# I2CKeypad.net
KiCad netlist of a schematic drawn in Altium Designer
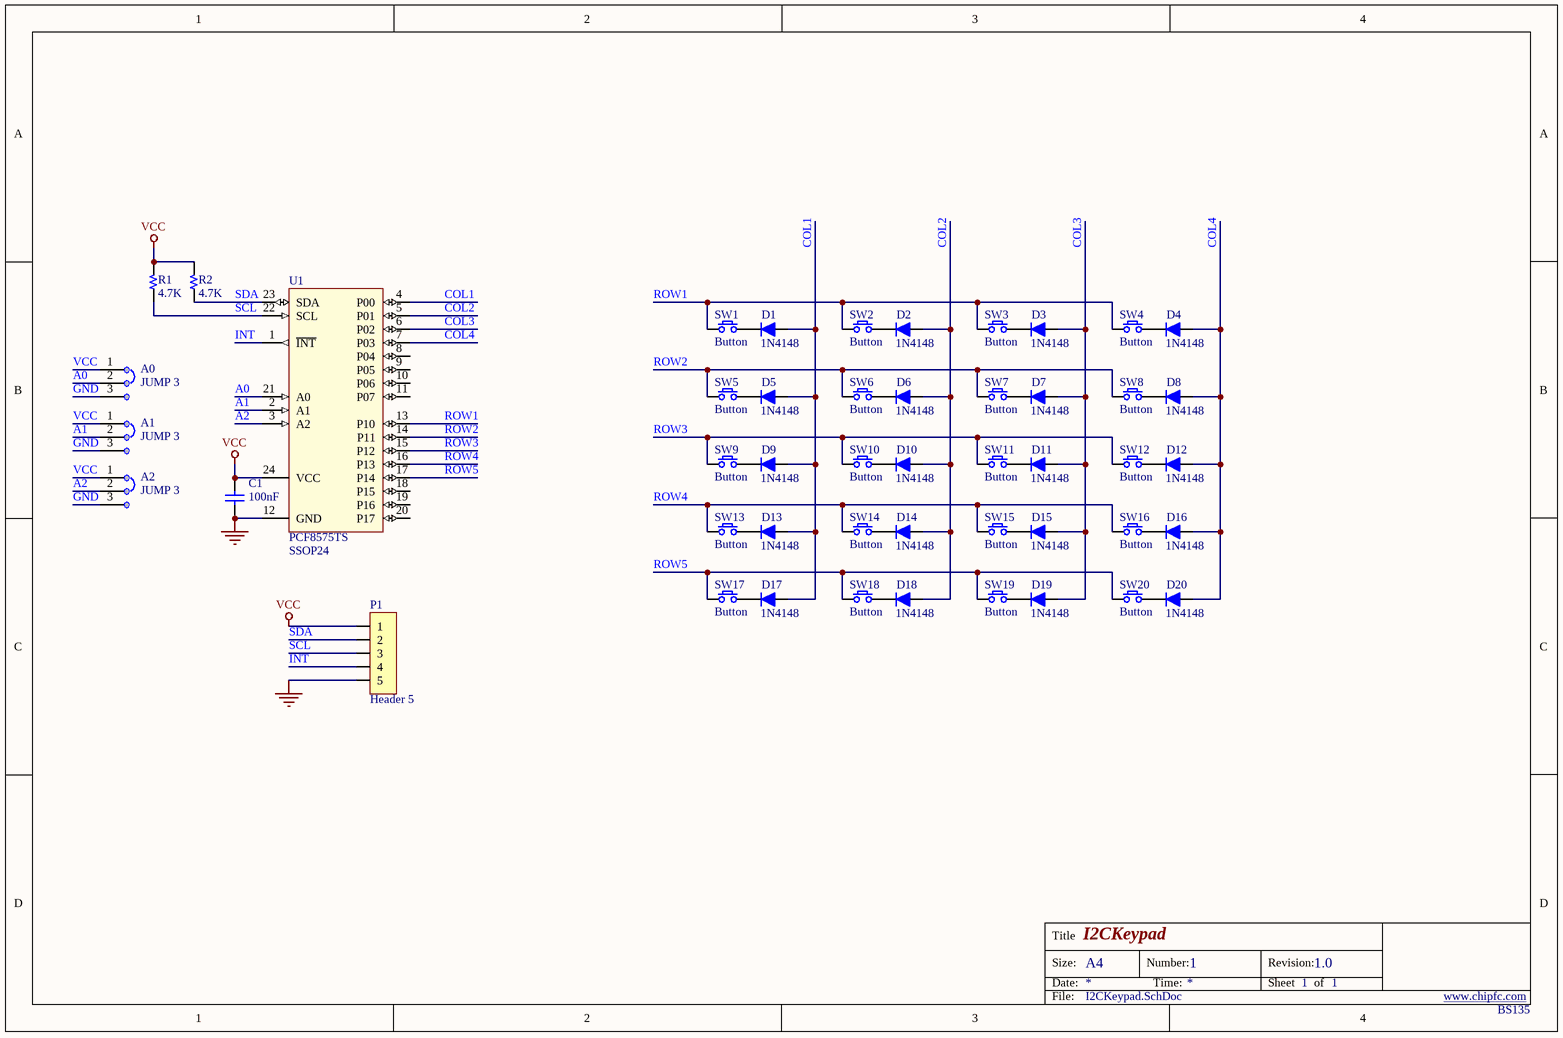
[diagram p0: I2CKeypad.SchDoc]

(export (version "E")
  (design (tool "Eeschema 10.0.6"))
  (components
    (comp (ref "A0") (value "JUMP 3") (footprint "JUMP3 SMD") (libsource (lib "ChipFC_Lib") (part "JUMP 3")))
    (comp (ref "A1") (value "JUMP 3") (footprint "JUMP3 SMD") (libsource (lib "ChipFC_Lib") (part "JUMP 3")))
    (comp (ref "A2") (value "JUMP 3") (footprint "JUMP3 SMD") (libsource (lib "ChipFC_Lib") (part "JUMP 3")))
    (comp (ref "C1")
      (value "100nF")
      (footprint "C 0805")
      (description "Capacitor non-pol")
      (libsource (lib "ChipFC_Lib") (part "Capacitor NP"))
    )
    (comp (ref "D1")
      (value "1N4148")
      (footprint "Diode SOD80C Wave")
      (description "Default Diode")
      (libsource (lib "ChipFC_Lib") (part "Diode"))
    )
    (comp (ref "D2")
      (value "1N4148")
      (footprint "Diode SOD80C Wave")
      (description "Default Diode")
      (libsource (lib "ChipFC_Lib") (part "Diode"))
    )
    (comp (ref "D3")
      (value "1N4148")
      (footprint "Diode SOD80C Wave")
      (description "Default Diode")
      (libsource (lib "ChipFC_Lib") (part "Diode"))
    )
    (comp (ref "D4")
      (value "1N4148")
      (footprint "Diode SOD80C Wave")
      (description "Default Diode")
      (libsource (lib "ChipFC_Lib") (part "Diode"))
    )
    (comp (ref "D5")
      (value "1N4148")
      (footprint "Diode SOD80C Wave")
      (description "Default Diode")
      (libsource (lib "ChipFC_Lib") (part "Diode"))
    )
    (comp (ref "D6")
      (value "1N4148")
      (footprint "Diode SOD80C Wave")
      (description "Default Diode")
      (libsource (lib "ChipFC_Lib") (part "Diode"))
    )
    (comp (ref "D7")
      (value "1N4148")
      (footprint "Diode SOD80C Wave")
      (description "Default Diode")
      (libsource (lib "ChipFC_Lib") (part "Diode"))
    )
    (comp (ref "D8")
      (value "1N4148")
      (footprint "Diode SOD80C Wave")
      (description "Default Diode")
      (libsource (lib "ChipFC_Lib") (part "Diode"))
    )
    (comp (ref "D9")
      (value "1N4148")
      (footprint "Diode SOD80C Wave")
      (description "Default Diode")
      (libsource (lib "ChipFC_Lib") (part "Diode"))
    )
    (comp (ref "D10")
      (value "1N4148")
      (footprint "Diode SOD80C Wave")
      (description "Default Diode")
      (libsource (lib "ChipFC_Lib") (part "Diode"))
    )
    (comp (ref "D11")
      (value "1N4148")
      (footprint "Diode SOD80C Wave")
      (description "Default Diode")
      (libsource (lib "ChipFC_Lib") (part "Diode"))
    )
    (comp (ref "D12")
      (value "1N4148")
      (footprint "Diode SOD80C Wave")
      (description "Default Diode")
      (libsource (lib "ChipFC_Lib") (part "Diode"))
    )
    (comp (ref "D13")
      (value "1N4148")
      (footprint "Diode SOD80C Wave")
      (description "Default Diode")
      (libsource (lib "ChipFC_Lib") (part "Diode"))
    )
    (comp (ref "D14")
      (value "1N4148")
      (footprint "Diode SOD80C Wave")
      (description "Default Diode")
      (libsource (lib "ChipFC_Lib") (part "Diode"))
    )
    (comp (ref "D15")
      (value "1N4148")
      (footprint "Diode SOD80C Wave")
      (description "Default Diode")
      (libsource (lib "ChipFC_Lib") (part "Diode"))
    )
    (comp (ref "D16")
      (value "1N4148")
      (footprint "Diode SOD80C Wave")
      (description "Default Diode")
      (libsource (lib "ChipFC_Lib") (part "Diode"))
    )
    (comp (ref "D17")
      (value "1N4148")
      (footprint "Diode SOD80C Wave")
      (description "Default Diode")
      (libsource (lib "ChipFC_Lib") (part "Diode"))
    )
    (comp (ref "D18")
      (value "1N4148")
      (footprint "Diode SOD80C Wave")
      (description "Default Diode")
      (libsource (lib "ChipFC_Lib") (part "Diode"))
    )
    (comp (ref "D19")
      (value "1N4148")
      (footprint "Diode SOD80C Wave")
      (description "Default Diode")
      (libsource (lib "ChipFC_Lib") (part "Diode"))
    )
    (comp (ref "D20")
      (value "1N4148")
      (footprint "Diode SOD80C Wave")
      (description "Default Diode")
      (libsource (lib "ChipFC_Lib") (part "Diode"))
    )
    (comp (ref "P1")
      (value "Header 5")
      (footprint "Header 5")
      (description "Header, 5-Pin")
      (libsource (lib "ChipFC_Lib") (part "Header 5"))
    )
    (comp (ref "R1")
      (value "4.7K")
      (footprint "R 0805")
      (description "Resistor")
      (libsource (lib "ChipFC_Lib") (part "Resistor"))
    )
    (comp (ref "R2")
      (value "4.7K")
      (footprint "R 0805")
      (description "Resistor")
      (libsource (lib "ChipFC_Lib") (part "Resistor"))
    )
    (comp (ref "SW1")
      (value "Button")
      (footprint "SW/2/DIP")
      (description "Tact switch 2 pin")
      (libsource (lib "ChipFC_Lib") (part "SW SPST"))
    )
    (comp (ref "SW2")
      (value "Button")
      (footprint "SW/2/DIP")
      (description "Tact switch 2 pin")
      (libsource (lib "ChipFC_Lib") (part "SW SPST"))
    )
    (comp (ref "SW3")
      (value "Button")
      (footprint "SW/2/DIP")
      (description "Tact switch 2 pin")
      (libsource (lib "ChipFC_Lib") (part "SW SPST"))
    )
    (comp (ref "SW4")
      (value "Button")
      (footprint "SW/2/DIP")
      (description "Tact switch 2 pin")
      (libsource (lib "ChipFC_Lib") (part "SW SPST"))
    )
    (comp (ref "SW5")
      (value "Button")
      (footprint "SW/2/DIP")
      (description "Tact switch 2 pin")
      (libsource (lib "ChipFC_Lib") (part "SW SPST"))
    )
    (comp (ref "SW6")
      (value "Button")
      (footprint "SW/2/DIP")
      (description "Tact switch 2 pin")
      (libsource (lib "ChipFC_Lib") (part "SW SPST"))
    )
    (comp (ref "SW7")
      (value "Button")
      (footprint "SW/2/DIP")
      (description "Tact switch 2 pin")
      (libsource (lib "ChipFC_Lib") (part "SW SPST"))
    )
    (comp (ref "SW8")
      (value "Button")
      (footprint "SW/2/DIP")
      (description "Tact switch 2 pin")
      (libsource (lib "ChipFC_Lib") (part "SW SPST"))
    )
    (comp (ref "SW9")
      (value "Button")
      (footprint "SW/2/DIP")
      (description "Tact switch 2 pin")
      (libsource (lib "ChipFC_Lib") (part "SW SPST"))
    )
    (comp (ref "SW10")
      (value "Button")
      (footprint "SW/2/DIP")
      (description "Tact switch 2 pin")
      (libsource (lib "ChipFC_Lib") (part "SW SPST"))
    )
    (comp (ref "SW11")
      (value "Button")
      (footprint "SW/2/DIP")
      (description "Tact switch 2 pin")
      (libsource (lib "ChipFC_Lib") (part "SW SPST"))
    )
    (comp (ref "SW12")
      (value "Button")
      (footprint "SW/2/DIP")
      (description "Tact switch 2 pin")
      (libsource (lib "ChipFC_Lib") (part "SW SPST"))
    )
    (comp (ref "SW13")
      (value "Button")
      (footprint "SW/2/DIP")
      (description "Tact switch 2 pin")
      (libsource (lib "ChipFC_Lib") (part "SW SPST"))
    )
    (comp (ref "SW14")
      (value "Button")
      (footprint "SW/2/DIP")
      (description "Tact switch 2 pin")
      (libsource (lib "ChipFC_Lib") (part "SW SPST"))
    )
    (comp (ref "SW15")
      (value "Button")
      (footprint "SW/2/DIP")
      (description "Tact switch 2 pin")
      (libsource (lib "ChipFC_Lib") (part "SW SPST"))
    )
    (comp (ref "SW16")
      (value "Button")
      (footprint "SW/2/DIP")
      (description "Tact switch 2 pin")
      (libsource (lib "ChipFC_Lib") (part "SW SPST"))
    )
    (comp (ref "SW17")
      (value "Button")
      (footprint "SW/2/DIP")
      (description "Tact switch 2 pin")
      (libsource (lib "ChipFC_Lib") (part "SW SPST"))
    )
    (comp (ref "SW18")
      (value "Button")
      (footprint "SW/2/DIP")
      (description "Tact switch 2 pin")
      (libsource (lib "ChipFC_Lib") (part "SW SPST"))
    )
    (comp (ref "SW19")
      (value "Button")
      (footprint "SW/2/DIP")
      (description "Tact switch 2 pin")
      (libsource (lib "ChipFC_Lib") (part "SW SPST"))
    )
    (comp (ref "SW20")
      (value "Button")
      (footprint "SW/2/DIP")
      (description "Tact switch 2 pin")
      (libsource (lib "ChipFC_Lib") (part "SW SPST"))
    )
    (comp (ref "U1")
      (value "PCF8575TS")
      (footprint "SSOP24/PCF8575TS")
      (description "PCF8575 Remote16-BIT I  2C AND SMBus I/O Expander  with Interrupt Output")
      (fields (field (name "PACKAGE") "SSOP24"))
      (libsource (lib "ChipFC_Lib") (part "PCF8575TS"))
    )
  )
  (nets
    (net (code "1") (name "/A0") (class "Default")
      (node (ref "A0") (pin "2") (pinfunction "2_2") (pintype "passive"))
      (node (ref "U1") (pin "21") (pinfunction "A0_21") (pintype "input"))
    )
    (net (code "2") (name "/A1") (class "Default")
      (node (ref "A1") (pin "2") (pinfunction "2_2") (pintype "passive"))
      (node (ref "U1") (pin "2") (pinfunction "A1_2") (pintype "input"))
    )
    (net (code "3") (name "/A2") (class "Default")
      (node (ref "A2") (pin "2") (pinfunction "2_2") (pintype "passive"))
      (node (ref "U1") (pin "3") (pinfunction "A2_3") (pintype "input"))
    )
    (net (code "4") (name "/COL1") (class "Default")
      (node (ref "D1") (pin "1") (pinfunction "A_1") (pintype "passive"))
      (node (ref "D13") (pin "1") (pinfunction "A_1") (pintype "passive"))
      (node (ref "D17") (pin "1") (pinfunction "A_1") (pintype "passive"))
      (node (ref "D5") (pin "1") (pinfunction "A_1") (pintype "passive"))
      (node (ref "D9") (pin "1") (pinfunction "A_1") (pintype "passive"))
      (node (ref "U1") (pin "4") (pinfunction "P00_4") (pintype "bidirectional"))
    )
    (net (code "5") (name "/COL2") (class "Default")
      (node (ref "D10") (pin "1") (pinfunction "A_1") (pintype "passive"))
      (node (ref "D14") (pin "1") (pinfunction "A_1") (pintype "passive"))
      (node (ref "D18") (pin "1") (pinfunction "A_1") (pintype "passive"))
      (node (ref "D2") (pin "1") (pinfunction "A_1") (pintype "passive"))
      (node (ref "D6") (pin "1") (pinfunction "A_1") (pintype "passive"))
      (node (ref "U1") (pin "5") (pinfunction "P01_5") (pintype "bidirectional"))
    )
    (net (code "6") (name "/COL3") (class "Default")
      (node (ref "D11") (pin "1") (pinfunction "A_1") (pintype "passive"))
      (node (ref "D15") (pin "1") (pinfunction "A_1") (pintype "passive"))
      (node (ref "D19") (pin "1") (pinfunction "A_1") (pintype "passive"))
      (node (ref "D3") (pin "1") (pinfunction "A_1") (pintype "passive"))
      (node (ref "D7") (pin "1") (pinfunction "A_1") (pintype "passive"))
      (node (ref "U1") (pin "6") (pinfunction "P02_6") (pintype "bidirectional"))
    )
    (net (code "7") (name "/COL4") (class "Default")
      (node (ref "D12") (pin "1") (pinfunction "A_1") (pintype "passive"))
      (node (ref "D16") (pin "1") (pinfunction "A_1") (pintype "passive"))
      (node (ref "D20") (pin "1") (pinfunction "A_1") (pintype "passive"))
      (node (ref "D4") (pin "1") (pinfunction "A_1") (pintype "passive"))
      (node (ref "D8") (pin "1") (pinfunction "A_1") (pintype "passive"))
      (node (ref "U1") (pin "7") (pinfunction "P03_7") (pintype "bidirectional"))
    )
    (net (code "8") (name "/INT") (class "Default")
      (node (ref "P1") (pin "4") (pinfunction "4_4") (pintype "passive"))
      (node (ref "U1") (pin "1") (pinfunction "~{INT}_1") (pintype "output"))
    )
    (net (code "9") (name "/ROW1") (class "Default")
      (node (ref "SW1") (pin "1") (pinfunction "1_1") (pintype "passive"))
      (node (ref "SW2") (pin "1") (pinfunction "1_1") (pintype "passive"))
      (node (ref "SW3") (pin "1") (pinfunction "1_1") (pintype "passive"))
      (node (ref "SW4") (pin "1") (pinfunction "1_1") (pintype "passive"))
      (node (ref "U1") (pin "13") (pinfunction "P10_13") (pintype "bidirectional"))
    )
    (net (code "10") (name "/ROW2") (class "Default")
      (node (ref "SW5") (pin "1") (pinfunction "1_1") (pintype "passive"))
      (node (ref "SW6") (pin "1") (pinfunction "1_1") (pintype "passive"))
      (node (ref "SW7") (pin "1") (pinfunction "1_1") (pintype "passive"))
      (node (ref "SW8") (pin "1") (pinfunction "1_1") (pintype "passive"))
      (node (ref "U1") (pin "14") (pinfunction "P11_14") (pintype "bidirectional"))
    )
    (net (code "11") (name "/ROW3") (class "Default")
      (node (ref "SW10") (pin "1") (pinfunction "1_1") (pintype "passive"))
      (node (ref "SW11") (pin "1") (pinfunction "1_1") (pintype "passive"))
      (node (ref "SW12") (pin "1") (pinfunction "1_1") (pintype "passive"))
      (node (ref "SW9") (pin "1") (pinfunction "1_1") (pintype "passive"))
      (node (ref "U1") (pin "15") (pinfunction "P12_15") (pintype "bidirectional"))
    )
    (net (code "12") (name "/ROW4") (class "Default")
      (node (ref "SW13") (pin "1") (pinfunction "1_1") (pintype "passive"))
      (node (ref "SW14") (pin "1") (pinfunction "1_1") (pintype "passive"))
      (node (ref "SW15") (pin "1") (pinfunction "1_1") (pintype "passive"))
      (node (ref "SW16") (pin "1") (pinfunction "1_1") (pintype "passive"))
      (node (ref "U1") (pin "16") (pinfunction "P13_16") (pintype "bidirectional"))
    )
    (net (code "13") (name "/ROW5") (class "Default")
      (node (ref "SW17") (pin "1") (pinfunction "1_1") (pintype "passive"))
      (node (ref "SW18") (pin "1") (pinfunction "1_1") (pintype "passive"))
      (node (ref "SW19") (pin "1") (pinfunction "1_1") (pintype "passive"))
      (node (ref "SW20") (pin "1") (pinfunction "1_1") (pintype "passive"))
      (node (ref "U1") (pin "17") (pinfunction "P14_17") (pintype "bidirectional"))
    )
    (net (code "14") (name "/SCL") (class "Default")
      (node (ref "P1") (pin "3") (pinfunction "3_3") (pintype "passive"))
      (node (ref "R1") (pin "1") (pinfunction "1_1") (pintype "passive"))
      (node (ref "U1") (pin "22") (pinfunction "SCL_22") (pintype "input"))
    )
    (net (code "15") (name "/SDA") (class "Default")
      (node (ref "P1") (pin "2") (pinfunction "2_2") (pintype "passive"))
      (node (ref "R2") (pin "1") (pinfunction "1_1") (pintype "passive"))
      (node (ref "U1") (pin "23") (pinfunction "SDA_23") (pintype "bidirectional"))
    )
    (net (code "16") (name "GND") (class "Default")
      (node (ref "A0") (pin "3") (pinfunction "3_3") (pintype "passive"))
      (node (ref "A1") (pin "3") (pinfunction "3_3") (pintype "passive"))
      (node (ref "A2") (pin "3") (pinfunction "3_3") (pintype "passive"))
      (node (ref "C1") (pin "2") (pinfunction "2_2") (pintype "passive"))
      (node (ref "P1") (pin "5") (pinfunction "5_5") (pintype "passive"))
      (node (ref "U1") (pin "12") (pinfunction "GND_12") (pintype "power_in"))
    )
    (net (code "17") (name "Net-(D1-K)") (class "Default")
      (node (ref "D1") (pin "2") (pinfunction "K_2") (pintype "passive"))
      (node (ref "SW1") (pin "2") (pinfunction "2_2") (pintype "passive"))
    )
    (net (code "18") (name "Net-(D2-K)") (class "Default")
      (node (ref "D2") (pin "2") (pinfunction "K_2") (pintype "passive"))
      (node (ref "SW2") (pin "2") (pinfunction "2_2") (pintype "passive"))
    )
    (net (code "19") (name "Net-(D3-K)") (class "Default")
      (node (ref "D3") (pin "2") (pinfunction "K_2") (pintype "passive"))
      (node (ref "SW3") (pin "2") (pinfunction "2_2") (pintype "passive"))
    )
    (net (code "20") (name "Net-(D4-K)") (class "Default")
      (node (ref "D4") (pin "2") (pinfunction "K_2") (pintype "passive"))
      (node (ref "SW4") (pin "2") (pinfunction "2_2") (pintype "passive"))
    )
    (net (code "21") (name "Net-(D5-K)") (class "Default")
      (node (ref "D5") (pin "2") (pinfunction "K_2") (pintype "passive"))
      (node (ref "SW5") (pin "2") (pinfunction "2_2") (pintype "passive"))
    )
    (net (code "22") (name "Net-(D6-K)") (class "Default")
      (node (ref "D6") (pin "2") (pinfunction "K_2") (pintype "passive"))
      (node (ref "SW6") (pin "2") (pinfunction "2_2") (pintype "passive"))
    )
    (net (code "23") (name "Net-(D7-K)") (class "Default")
      (node (ref "D7") (pin "2") (pinfunction "K_2") (pintype "passive"))
      (node (ref "SW7") (pin "2") (pinfunction "2_2") (pintype "passive"))
    )
    (net (code "24") (name "Net-(D8-K)") (class "Default")
      (node (ref "D8") (pin "2") (pinfunction "K_2") (pintype "passive"))
      (node (ref "SW8") (pin "2") (pinfunction "2_2") (pintype "passive"))
    )
    (net (code "25") (name "Net-(D9-K)") (class "Default")
      (node (ref "D9") (pin "2") (pinfunction "K_2") (pintype "passive"))
      (node (ref "SW9") (pin "2") (pinfunction "2_2") (pintype "passive"))
    )
    (net (code "26") (name "Net-(D10-K)") (class "Default")
      (node (ref "D10") (pin "2") (pinfunction "K_2") (pintype "passive"))
      (node (ref "SW10") (pin "2") (pinfunction "2_2") (pintype "passive"))
    )
    (net (code "27") (name "Net-(D11-K)") (class "Default")
      (node (ref "D11") (pin "2") (pinfunction "K_2") (pintype "passive"))
      (node (ref "SW11") (pin "2") (pinfunction "2_2") (pintype "passive"))
    )
    (net (code "28") (name "Net-(D12-K)") (class "Default")
      (node (ref "D12") (pin "2") (pinfunction "K_2") (pintype "passive"))
      (node (ref "SW12") (pin "2") (pinfunction "2_2") (pintype "passive"))
    )
    (net (code "29") (name "Net-(D13-K)") (class "Default")
      (node (ref "D13") (pin "2") (pinfunction "K_2") (pintype "passive"))
      (node (ref "SW13") (pin "2") (pinfunction "2_2") (pintype "passive"))
    )
    (net (code "30") (name "Net-(D14-K)") (class "Default")
      (node (ref "D14") (pin "2") (pinfunction "K_2") (pintype "passive"))
      (node (ref "SW14") (pin "2") (pinfunction "2_2") (pintype "passive"))
    )
    (net (code "31") (name "Net-(D15-K)") (class "Default")
      (node (ref "D15") (pin "2") (pinfunction "K_2") (pintype "passive"))
      (node (ref "SW15") (pin "2") (pinfunction "2_2") (pintype "passive"))
    )
    (net (code "32") (name "Net-(D16-K)") (class "Default")
      (node (ref "D16") (pin "2") (pinfunction "K_2") (pintype "passive"))
      (node (ref "SW16") (pin "2") (pinfunction "2_2") (pintype "passive"))
    )
    (net (code "33") (name "Net-(D17-K)") (class "Default")
      (node (ref "D17") (pin "2") (pinfunction "K_2") (pintype "passive"))
      (node (ref "SW17") (pin "2") (pinfunction "2_2") (pintype "passive"))
    )
    (net (code "34") (name "Net-(D18-K)") (class "Default")
      (node (ref "D18") (pin "2") (pinfunction "K_2") (pintype "passive"))
      (node (ref "SW18") (pin "2") (pinfunction "2_2") (pintype "passive"))
    )
    (net (code "35") (name "Net-(D19-K)") (class "Default")
      (node (ref "D19") (pin "2") (pinfunction "K_2") (pintype "passive"))
      (node (ref "SW19") (pin "2") (pinfunction "2_2") (pintype "passive"))
    )
    (net (code "36") (name "Net-(D20-K)") (class "Default")
      (node (ref "D20") (pin "2") (pinfunction "K_2") (pintype "passive"))
      (node (ref "SW20") (pin "2") (pinfunction "2_2") (pintype "passive"))
    )
    (net (code "37") (name "VCC") (class "Default")
      (node (ref "A0") (pin "1") (pinfunction "1_1") (pintype "passive"))
      (node (ref "A1") (pin "1") (pinfunction "1_1") (pintype "passive"))
      (node (ref "A2") (pin "1") (pinfunction "1_1") (pintype "passive"))
      (node (ref "C1") (pin "1") (pinfunction "1_1") (pintype "passive"))
      (node (ref "P1") (pin "1") (pinfunction "1_1") (pintype "passive"))
      (node (ref "R1") (pin "2") (pinfunction "2_2") (pintype "passive"))
      (node (ref "R2") (pin "2") (pinfunction "2_2") (pintype "passive"))
      (node (ref "U1") (pin "24") (pinfunction "VCC_24") (pintype "power_in"))
    )
    (net (code "38") (name "unconnected-(U1-P04-Pad8)") (class "Default")
      (node (ref "U1") (pin "8") (pinfunction "P04_8") (pintype "bidirectional"))
    )
    (net (code "39") (name "unconnected-(U1-P05-Pad9)") (class "Default")
      (node (ref "U1") (pin "9") (pinfunction "P05_9") (pintype "bidirectional"))
    )
    (net (code "40") (name "unconnected-(U1-P06-Pad10)") (class "Default")
      (node (ref "U1") (pin "10") (pinfunction "P06_10") (pintype "bidirectional"))
    )
    (net (code "41") (name "unconnected-(U1-P07-Pad11)") (class "Default")
      (node (ref "U1") (pin "11") (pinfunction "P07_11") (pintype "bidirectional"))
    )
    (net (code "42") (name "unconnected-(U1-P15-Pad18)") (class "Default")
      (node (ref "U1") (pin "18") (pinfunction "P15_18") (pintype "bidirectional"))
    )
    (net (code "43") (name "unconnected-(U1-P16-Pad19)") (class "Default")
      (node (ref "U1") (pin "19") (pinfunction "P16_19") (pintype "bidirectional"))
    )
    (net (code "44") (name "unconnected-(U1-P17-Pad20)") (class "Default")
      (node (ref "U1") (pin "20") (pinfunction "P17_20") (pintype "bidirectional"))
    )
  )
)
